# PCB-SSB-2x4b.net
KiCad netlist of a schematic drawn in EAGLE
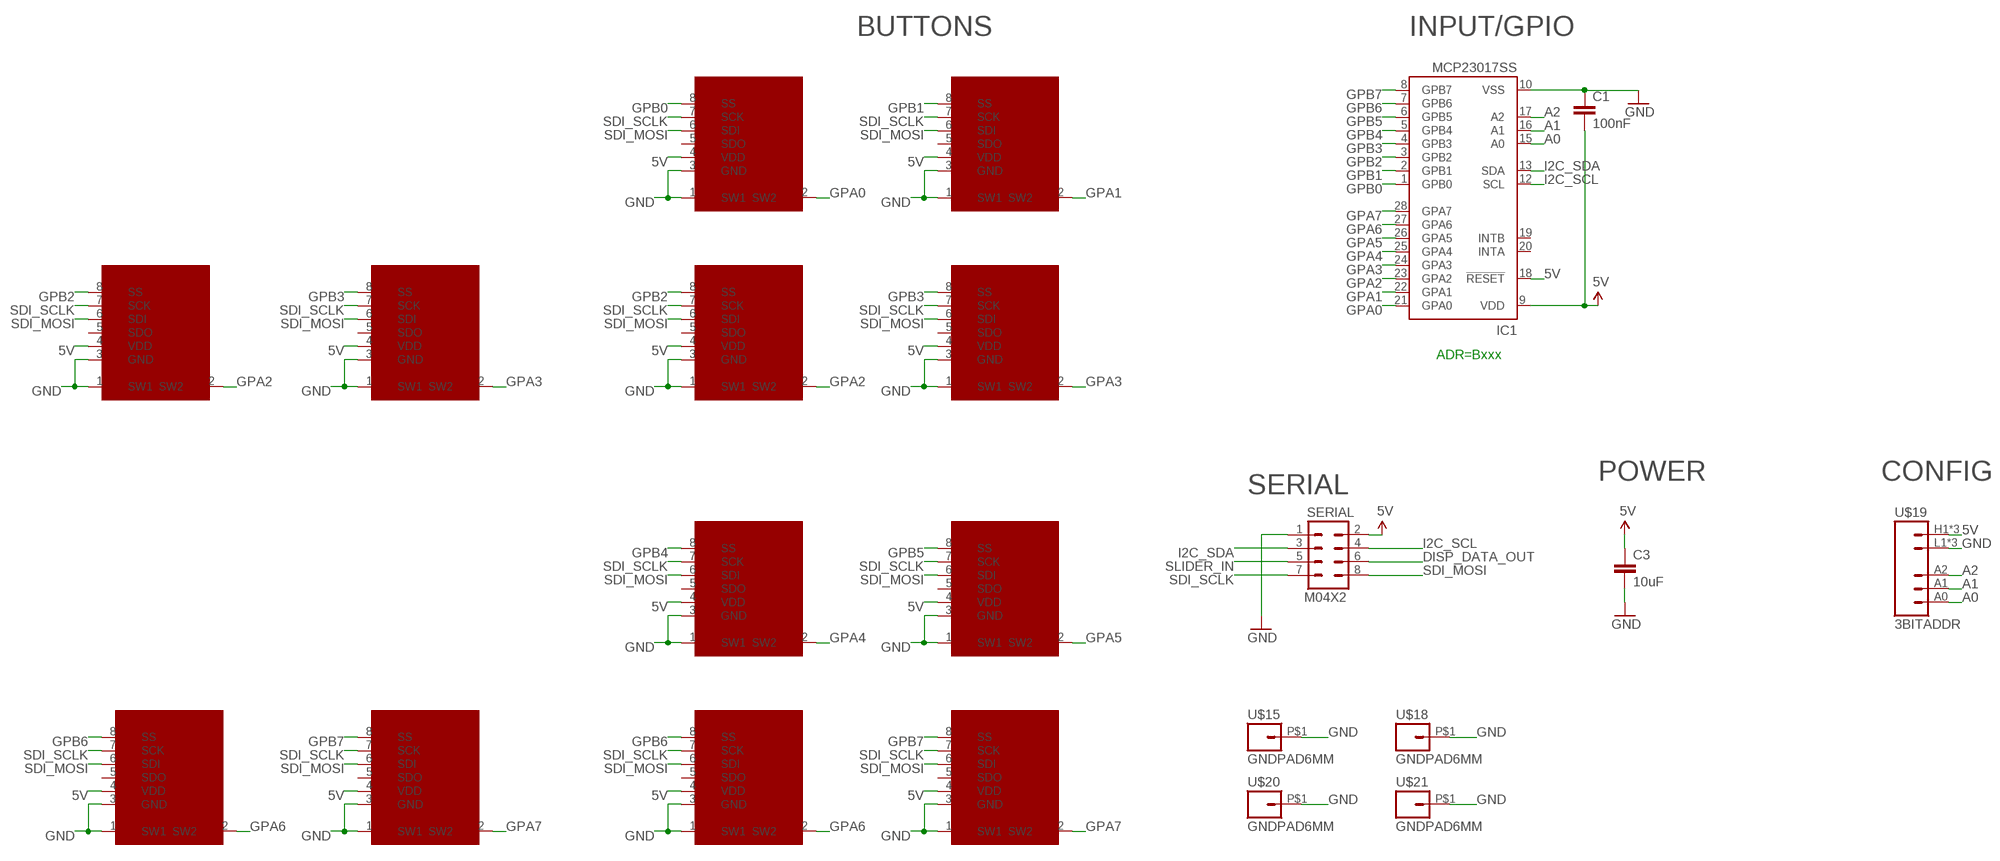
[diagram p0: schematic, sheet 1]

(export (version "E")
  (design (tool "Eeschema 10.0.6"))
  (components
    (comp (ref "C1")
      (value "100nF")
      (footprint "eagle-import:0603-CAP")
      (libsource (lib "eagle-import") (part "CAP0603-CAP"))
    )
    (comp (ref "C3")
      (value "10uF")
      (footprint "eagle-import:0805")
      (libsource (lib "eagle-import") (part "CAP0805"))
    )
    (comp (ref "IC1")
      (value "MCP23017SS")
      (footprint "eagle-import:SSOP28")
      (fields
        (field (name "MF") "MICROCHIP")
        (field (name "MPN") "MCP23017-E/SS")
        (field (name "MPN_1") "MCP23017-E/SS")
        (field (name "OC_FARNELL") "1467674")
        (field (name "OC_NEWARK") "31K2960")
      )
      (libsource (lib "eagle-import") (part "MCP23017SS"))
    )
    (comp (ref "SERIAL")
      (value "M04X2")
      (footprint "eagle-import:2X4")
      (libsource (lib "eagle-import") (part "M04X2"))
    )
    (comp (ref "SSW1")
      (value "SMART_SWITCHSMART_SWITCH_8PIN")
      (footprint "eagle-import:SMART_SWITCH")
      (libsource (lib "eagle-import") (part "SMART_SWITCHSMART_SWITCH_8PIN"))
    )
    (comp (ref "SSW2")
      (value "SMART_SWITCHSMART_SWITCH_8PIN")
      (footprint "eagle-import:SMART_SWITCH")
      (libsource (lib "eagle-import") (part "SMART_SWITCHSMART_SWITCH_8PIN"))
    )
    (comp (ref "SSW3")
      (value "SMART_SWITCHSMART_SWITCH_8PIN")
      (footprint "eagle-import:SMART_SWITCH")
      (libsource (lib "eagle-import") (part "SMART_SWITCHSMART_SWITCH_8PIN"))
    )
    (comp (ref "SSW3ALT")
      (value "SMART_SWITCHSMART_SWITCH_8PIN")
      (footprint "eagle-import:SMART_SWITCH")
      (libsource (lib "eagle-import") (part "SMART_SWITCHSMART_SWITCH_8PIN"))
    )
    (comp (ref "SSW4")
      (value "SMART_SWITCHSMART_SWITCH_8PIN")
      (footprint "eagle-import:SMART_SWITCH")
      (libsource (lib "eagle-import") (part "SMART_SWITCHSMART_SWITCH_8PIN"))
    )
    (comp (ref "SSW4ALT")
      (value "SMART_SWITCHSMART_SWITCH_8PIN")
      (footprint "eagle-import:SMART_SWITCH")
      (libsource (lib "eagle-import") (part "SMART_SWITCHSMART_SWITCH_8PIN"))
    )
    (comp (ref "SSW5")
      (value "SMART_SWITCHSMART_SWITCH_8PIN")
      (footprint "eagle-import:SMART_SWITCH")
      (libsource (lib "eagle-import") (part "SMART_SWITCHSMART_SWITCH_8PIN"))
    )
    (comp (ref "SSW6")
      (value "SMART_SWITCHSMART_SWITCH_8PIN")
      (footprint "eagle-import:SMART_SWITCH")
      (libsource (lib "eagle-import") (part "SMART_SWITCHSMART_SWITCH_8PIN"))
    )
    (comp (ref "SSW7")
      (value "SMART_SWITCHSMART_SWITCH_8PIN")
      (footprint "eagle-import:SMART_SWITCH")
      (libsource (lib "eagle-import") (part "SMART_SWITCHSMART_SWITCH_8PIN"))
    )
    (comp (ref "SSW7ALT")
      (value "SMART_SWITCHSMART_SWITCH_8PIN")
      (footprint "eagle-import:SMART_SWITCH")
      (libsource (lib "eagle-import") (part "SMART_SWITCHSMART_SWITCH_8PIN"))
    )
    (comp (ref "SSW8")
      (value "SMART_SWITCHSMART_SWITCH_8PIN")
      (footprint "eagle-import:SMART_SWITCH")
      (libsource (lib "eagle-import") (part "SMART_SWITCHSMART_SWITCH_8PIN"))
    )
    (comp (ref "SSW8ALT")
      (value "SMART_SWITCHSMART_SWITCH_8PIN")
      (footprint "eagle-import:SMART_SWITCH")
      (libsource (lib "eagle-import") (part "SMART_SWITCHSMART_SWITCH_8PIN"))
    )
    (comp (ref "U$15")
      (value "GNDPAD6MM")
      (footprint "eagle-import:3.2MMPAD6MM")
      (libsource (lib "eagle-import") (part "GNDPAD6MM"))
    )
    (comp (ref "U$18")
      (value "GNDPAD6MM")
      (footprint "eagle-import:3.2MMPAD6MM")
      (libsource (lib "eagle-import") (part "GNDPAD6MM"))
    )
    (comp (ref "U$19")
      (value "3BITADDR")
      (footprint "eagle-import:3BITADDR")
      (libsource (lib "eagle-import") (part "3BITADDR"))
    )
    (comp (ref "U$20")
      (value "GNDPAD6MM")
      (footprint "eagle-import:3.2MMPAD6MM")
      (libsource (lib "eagle-import") (part "GNDPAD6MM"))
    )
    (comp (ref "U$21")
      (value "GNDPAD6MM")
      (footprint "eagle-import:3.2MMPAD6MM")
      (libsource (lib "eagle-import") (part "GNDPAD6MM"))
    )
  )
  (nets
    (net (code "1") (name "/A0") (class "Default")
      (node (ref "IC1") (pin "15") (pinfunction "A0_15") (pintype "input"))
      (node (ref "U$19") (pin "A0") (pinfunction "A0_A0") (pintype "passive"))
    )
    (net (code "2") (name "/A1") (class "Default")
      (node (ref "IC1") (pin "16") (pinfunction "A1_16") (pintype "input"))
      (node (ref "U$19") (pin "A1") (pinfunction "A1_A1") (pintype "passive"))
    )
    (net (code "3") (name "/A2") (class "Default")
      (node (ref "IC1") (pin "17") (pinfunction "A2_17") (pintype "input"))
      (node (ref "U$19") (pin "A2") (pinfunction "A2_A2") (pintype "passive"))
    )
    (net (code "4") (name "/DISP_DATA_OUT") (class "Default")
      (node (ref "SERIAL") (pin "6") (pinfunction "6_6") (pintype "passive"))
    )
    (net (code "5") (name "/GPA0") (class "Default")
      (node (ref "IC1") (pin "21") (pinfunction "GPA0_21") (pintype "bidirectional"))
      (node (ref "SSW1") (pin "2") (pinfunction "SW2_2") (pintype "bidirectional"))
    )
    (net (code "6") (name "/GPA1") (class "Default")
      (node (ref "IC1") (pin "22") (pinfunction "GPA1_22") (pintype "bidirectional"))
      (node (ref "SSW2") (pin "2") (pinfunction "SW2_2") (pintype "bidirectional"))
    )
    (net (code "7") (name "/GPA2") (class "Default")
      (node (ref "IC1") (pin "23") (pinfunction "GPA2_23") (pintype "bidirectional"))
      (node (ref "SSW3") (pin "2") (pinfunction "SW2_2") (pintype "bidirectional"))
      (node (ref "SSW3ALT") (pin "2") (pinfunction "SW2_2") (pintype "bidirectional"))
    )
    (net (code "8") (name "/GPA3") (class "Default")
      (node (ref "IC1") (pin "24") (pinfunction "GPA3_24") (pintype "bidirectional"))
      (node (ref "SSW4") (pin "2") (pinfunction "SW2_2") (pintype "bidirectional"))
      (node (ref "SSW4ALT") (pin "2") (pinfunction "SW2_2") (pintype "bidirectional"))
    )
    (net (code "9") (name "/GPA4") (class "Default")
      (node (ref "IC1") (pin "25") (pinfunction "GPA4_25") (pintype "bidirectional"))
      (node (ref "SSW5") (pin "2") (pinfunction "SW2_2") (pintype "bidirectional"))
    )
    (net (code "10") (name "/GPA5") (class "Default")
      (node (ref "IC1") (pin "26") (pinfunction "GPA5_26") (pintype "bidirectional"))
      (node (ref "SSW6") (pin "2") (pinfunction "SW2_2") (pintype "bidirectional"))
    )
    (net (code "11") (name "/GPA6") (class "Default")
      (node (ref "IC1") (pin "27") (pinfunction "GPA6_27") (pintype "bidirectional"))
      (node (ref "SSW7") (pin "2") (pinfunction "SW2_2") (pintype "bidirectional"))
      (node (ref "SSW7ALT") (pin "2") (pinfunction "SW2_2") (pintype "bidirectional"))
    )
    (net (code "12") (name "/GPA7") (class "Default")
      (node (ref "IC1") (pin "28") (pinfunction "GPA7_28") (pintype "bidirectional"))
      (node (ref "SSW8") (pin "2") (pinfunction "SW2_2") (pintype "bidirectional"))
      (node (ref "SSW8ALT") (pin "2") (pinfunction "SW2_2") (pintype "bidirectional"))
    )
    (net (code "13") (name "/GPB0") (class "Default")
      (node (ref "IC1") (pin "1") (pinfunction "GPB0_1") (pintype "bidirectional"))
      (node (ref "SSW1") (pin "8") (pinfunction "SS_8") (pintype "bidirectional"))
    )
    (net (code "14") (name "/GPB1") (class "Default")
      (node (ref "IC1") (pin "2") (pinfunction "GPB1_2") (pintype "bidirectional"))
      (node (ref "SSW2") (pin "8") (pinfunction "SS_8") (pintype "bidirectional"))
    )
    (net (code "15") (name "/GPB2") (class "Default")
      (node (ref "IC1") (pin "3") (pinfunction "GPB2_3") (pintype "bidirectional"))
      (node (ref "SSW3") (pin "8") (pinfunction "SS_8") (pintype "bidirectional"))
      (node (ref "SSW3ALT") (pin "8") (pinfunction "SS_8") (pintype "bidirectional"))
    )
    (net (code "16") (name "/GPB3") (class "Default")
      (node (ref "IC1") (pin "4") (pinfunction "GPB3_4") (pintype "bidirectional"))
      (node (ref "SSW4") (pin "8") (pinfunction "SS_8") (pintype "bidirectional"))
      (node (ref "SSW4ALT") (pin "8") (pinfunction "SS_8") (pintype "bidirectional"))
    )
    (net (code "17") (name "/GPB4") (class "Default")
      (node (ref "IC1") (pin "5") (pinfunction "GPB4_5") (pintype "bidirectional"))
      (node (ref "SSW5") (pin "8") (pinfunction "SS_8") (pintype "bidirectional"))
    )
    (net (code "18") (name "/GPB5") (class "Default")
      (node (ref "IC1") (pin "6") (pinfunction "GPB5_6") (pintype "bidirectional"))
      (node (ref "SSW6") (pin "8") (pinfunction "SS_8") (pintype "bidirectional"))
    )
    (net (code "19") (name "/GPB6") (class "Default")
      (node (ref "IC1") (pin "7") (pinfunction "GPB6_7") (pintype "bidirectional"))
      (node (ref "SSW7") (pin "8") (pinfunction "SS_8") (pintype "bidirectional"))
      (node (ref "SSW7ALT") (pin "8") (pinfunction "SS_8") (pintype "bidirectional"))
    )
    (net (code "20") (name "/GPB7") (class "Default")
      (node (ref "IC1") (pin "8") (pinfunction "GPB7_8") (pintype "bidirectional"))
      (node (ref "SSW8") (pin "8") (pinfunction "SS_8") (pintype "bidirectional"))
      (node (ref "SSW8ALT") (pin "8") (pinfunction "SS_8") (pintype "bidirectional"))
    )
    (net (code "21") (name "/I2C_SCL") (class "Default")
      (node (ref "IC1") (pin "12") (pinfunction "SCL_12") (pintype "input"))
      (node (ref "SERIAL") (pin "4") (pinfunction "4_4") (pintype "passive"))
    )
    (net (code "22") (name "/I2C_SDA") (class "Default")
      (node (ref "IC1") (pin "13") (pinfunction "SDA_13") (pintype "bidirectional"))
      (node (ref "SERIAL") (pin "3") (pinfunction "3_3") (pintype "passive"))
    )
    (net (code "23") (name "/SDI_MOSI") (class "Default")
      (node (ref "SERIAL") (pin "8") (pinfunction "8_8") (pintype "passive"))
      (node (ref "SSW1") (pin "6") (pinfunction "SDI_6") (pintype "bidirectional"))
      (node (ref "SSW2") (pin "6") (pinfunction "SDI_6") (pintype "bidirectional"))
      (node (ref "SSW3") (pin "6") (pinfunction "SDI_6") (pintype "bidirectional"))
      (node (ref "SSW3ALT") (pin "6") (pinfunction "SDI_6") (pintype "bidirectional"))
      (node (ref "SSW4") (pin "6") (pinfunction "SDI_6") (pintype "bidirectional"))
      (node (ref "SSW4ALT") (pin "6") (pinfunction "SDI_6") (pintype "bidirectional"))
      (node (ref "SSW5") (pin "6") (pinfunction "SDI_6") (pintype "bidirectional"))
      (node (ref "SSW6") (pin "6") (pinfunction "SDI_6") (pintype "bidirectional"))
      (node (ref "SSW7") (pin "6") (pinfunction "SDI_6") (pintype "bidirectional"))
      (node (ref "SSW7ALT") (pin "6") (pinfunction "SDI_6") (pintype "bidirectional"))
      (node (ref "SSW8") (pin "6") (pinfunction "SDI_6") (pintype "bidirectional"))
      (node (ref "SSW8ALT") (pin "6") (pinfunction "SDI_6") (pintype "bidirectional"))
    )
    (net (code "24") (name "/SDI_SCLK") (class "Default")
      (node (ref "SERIAL") (pin "7") (pinfunction "7_7") (pintype "passive"))
      (node (ref "SSW1") (pin "7") (pinfunction "SCK_7") (pintype "bidirectional"))
      (node (ref "SSW2") (pin "7") (pinfunction "SCK_7") (pintype "bidirectional"))
      (node (ref "SSW3") (pin "7") (pinfunction "SCK_7") (pintype "bidirectional"))
      (node (ref "SSW3ALT") (pin "7") (pinfunction "SCK_7") (pintype "bidirectional"))
      (node (ref "SSW4") (pin "7") (pinfunction "SCK_7") (pintype "bidirectional"))
      (node (ref "SSW4ALT") (pin "7") (pinfunction "SCK_7") (pintype "bidirectional"))
      (node (ref "SSW5") (pin "7") (pinfunction "SCK_7") (pintype "bidirectional"))
      (node (ref "SSW6") (pin "7") (pinfunction "SCK_7") (pintype "bidirectional"))
      (node (ref "SSW7") (pin "7") (pinfunction "SCK_7") (pintype "bidirectional"))
      (node (ref "SSW7ALT") (pin "7") (pinfunction "SCK_7") (pintype "bidirectional"))
      (node (ref "SSW8") (pin "7") (pinfunction "SCK_7") (pintype "bidirectional"))
      (node (ref "SSW8ALT") (pin "7") (pinfunction "SCK_7") (pintype "bidirectional"))
    )
    (net (code "25") (name "/SLIDER_IN") (class "Default")
      (node (ref "SERIAL") (pin "5") (pinfunction "5_5") (pintype "passive"))
    )
    (net (code "26") (name "5V") (class "Default")
      (node (ref "C1") (pin "2") (pinfunction "2_2") (pintype "passive"))
      (node (ref "C3") (pin "1") (pinfunction "1_1") (pintype "passive"))
      (node (ref "IC1") (pin "18") (pinfunction "~{RESET}_18") (pintype "input"))
      (node (ref "IC1") (pin "9") (pinfunction "VDD_9") (pintype "power_in"))
      (node (ref "SERIAL") (pin "2") (pinfunction "2_2") (pintype "passive"))
      (node (ref "SSW1") (pin "4") (pinfunction "VDD_4") (pintype "bidirectional"))
      (node (ref "SSW2") (pin "4") (pinfunction "VDD_4") (pintype "bidirectional"))
      (node (ref "SSW3") (pin "4") (pinfunction "VDD_4") (pintype "bidirectional"))
      (node (ref "SSW3ALT") (pin "4") (pinfunction "VDD_4") (pintype "bidirectional"))
      (node (ref "SSW4") (pin "4") (pinfunction "VDD_4") (pintype "bidirectional"))
      (node (ref "SSW4ALT") (pin "4") (pinfunction "VDD_4") (pintype "bidirectional"))
      (node (ref "SSW5") (pin "4") (pinfunction "VDD_4") (pintype "bidirectional"))
      (node (ref "SSW6") (pin "4") (pinfunction "VDD_4") (pintype "bidirectional"))
      (node (ref "SSW7") (pin "4") (pinfunction "VDD_4") (pintype "bidirectional"))
      (node (ref "SSW7ALT") (pin "4") (pinfunction "VDD_4") (pintype "bidirectional"))
      (node (ref "SSW8") (pin "4") (pinfunction "VDD_4") (pintype "bidirectional"))
      (node (ref "SSW8ALT") (pin "4") (pinfunction "VDD_4") (pintype "bidirectional"))
      (node (ref "U$19") (pin "H1") (pinfunction "VCC_H1") (pintype "passive"))
      (node (ref "U$19") (pin "H2") (pinfunction "VCC_H2") (pintype "passive"))
      (node (ref "U$19") (pin "H3") (pinfunction "VCC_H3") (pintype "passive"))
    )
    (net (code "27") (name "GND") (class "Default")
      (node (ref "C1") (pin "1") (pinfunction "1_1") (pintype "passive"))
      (node (ref "C3") (pin "2") (pinfunction "2_2") (pintype "passive"))
      (node (ref "IC1") (pin "10") (pinfunction "VSS_10") (pintype "power_in"))
      (node (ref "SERIAL") (pin "1") (pinfunction "1_1") (pintype "passive"))
      (node (ref "SSW1") (pin "1") (pinfunction "SW1_1") (pintype "bidirectional"))
      (node (ref "SSW1") (pin "3") (pinfunction "GND_3") (pintype "bidirectional"))
      (node (ref "SSW2") (pin "1") (pinfunction "SW1_1") (pintype "bidirectional"))
      (node (ref "SSW2") (pin "3") (pinfunction "GND_3") (pintype "bidirectional"))
      (node (ref "SSW3") (pin "1") (pinfunction "SW1_1") (pintype "bidirectional"))
      (node (ref "SSW3") (pin "3") (pinfunction "GND_3") (pintype "bidirectional"))
      (node (ref "SSW3ALT") (pin "1") (pinfunction "SW1_1") (pintype "bidirectional"))
      (node (ref "SSW3ALT") (pin "3") (pinfunction "GND_3") (pintype "bidirectional"))
      (node (ref "SSW4") (pin "1") (pinfunction "SW1_1") (pintype "bidirectional"))
      (node (ref "SSW4") (pin "3") (pinfunction "GND_3") (pintype "bidirectional"))
      (node (ref "SSW4ALT") (pin "1") (pinfunction "SW1_1") (pintype "bidirectional"))
      (node (ref "SSW4ALT") (pin "3") (pinfunction "GND_3") (pintype "bidirectional"))
      (node (ref "SSW5") (pin "1") (pinfunction "SW1_1") (pintype "bidirectional"))
      (node (ref "SSW5") (pin "3") (pinfunction "GND_3") (pintype "bidirectional"))
      (node (ref "SSW6") (pin "1") (pinfunction "SW1_1") (pintype "bidirectional"))
      (node (ref "SSW6") (pin "3") (pinfunction "GND_3") (pintype "bidirectional"))
      (node (ref "SSW7") (pin "1") (pinfunction "SW1_1") (pintype "bidirectional"))
      (node (ref "SSW7") (pin "3") (pinfunction "GND_3") (pintype "bidirectional"))
      (node (ref "SSW7ALT") (pin "1") (pinfunction "SW1_1") (pintype "bidirectional"))
      (node (ref "SSW7ALT") (pin "3") (pinfunction "GND_3") (pintype "bidirectional"))
      (node (ref "SSW8") (pin "1") (pinfunction "SW1_1") (pintype "bidirectional"))
      (node (ref "SSW8") (pin "3") (pinfunction "GND_3") (pintype "bidirectional"))
      (node (ref "SSW8ALT") (pin "1") (pinfunction "SW1_1") (pintype "bidirectional"))
      (node (ref "SSW8ALT") (pin "3") (pinfunction "GND_3") (pintype "bidirectional"))
      (node (ref "U$15") (pin "P$1") (pinfunction "1_P$1") (pintype "passive"))
      (node (ref "U$18") (pin "P$1") (pinfunction "1_P$1") (pintype "passive"))
      (node (ref "U$19") (pin "L1") (pinfunction "GND_L1") (pintype "passive"))
      (node (ref "U$19") (pin "L2") (pinfunction "GND_L2") (pintype "passive"))
      (node (ref "U$19") (pin "L3") (pinfunction "GND_L3") (pintype "passive"))
      (node (ref "U$20") (pin "P$1") (pinfunction "1_P$1") (pintype "passive"))
      (node (ref "U$21") (pin "P$1") (pinfunction "1_P$1") (pintype "passive"))
    )
    (net (code "28") (name "unconnected-(IC1-INTA-Pad20)") (class "Default")
      (node (ref "IC1") (pin "20") (pinfunction "INTA_20") (pintype "output"))
    )
    (net (code "29") (name "unconnected-(IC1-INTB-Pad19)") (class "Default")
      (node (ref "IC1") (pin "19") (pinfunction "INTB_19") (pintype "output"))
    )
    (net (code "30") (name "unconnected-(SSW1-SDO-Pad5)") (class "Default")
      (node (ref "SSW1") (pin "5") (pinfunction "SDO_5") (pintype "bidirectional"))
    )
    (net (code "31") (name "unconnected-(SSW2-SDO-Pad5)") (class "Default")
      (node (ref "SSW2") (pin "5") (pinfunction "SDO_5") (pintype "bidirectional"))
    )
    (net (code "32") (name "unconnected-(SSW3-SDO-Pad5)") (class "Default")
      (node (ref "SSW3") (pin "5") (pinfunction "SDO_5") (pintype "bidirectional"))
    )
    (net (code "33") (name "unconnected-(SSW3ALT-SDO-Pad5)") (class "Default")
      (node (ref "SSW3ALT") (pin "5") (pinfunction "SDO_5") (pintype "bidirectional"))
    )
    (net (code "34") (name "unconnected-(SSW4-SDO-Pad5)") (class "Default")
      (node (ref "SSW4") (pin "5") (pinfunction "SDO_5") (pintype "bidirectional"))
    )
    (net (code "35") (name "unconnected-(SSW4ALT-SDO-Pad5)") (class "Default")
      (node (ref "SSW4ALT") (pin "5") (pinfunction "SDO_5") (pintype "bidirectional"))
    )
    (net (code "36") (name "unconnected-(SSW5-SDO-Pad5)") (class "Default")
      (node (ref "SSW5") (pin "5") (pinfunction "SDO_5") (pintype "bidirectional"))
    )
    (net (code "37") (name "unconnected-(SSW6-SDO-Pad5)") (class "Default")
      (node (ref "SSW6") (pin "5") (pinfunction "SDO_5") (pintype "bidirectional"))
    )
    (net (code "38") (name "unconnected-(SSW7-SDO-Pad5)") (class "Default")
      (node (ref "SSW7") (pin "5") (pinfunction "SDO_5") (pintype "bidirectional"))
    )
    (net (code "39") (name "unconnected-(SSW7ALT-SDO-Pad5)") (class "Default")
      (node (ref "SSW7ALT") (pin "5") (pinfunction "SDO_5") (pintype "bidirectional"))
    )
    (net (code "40") (name "unconnected-(SSW8-SDO-Pad5)") (class "Default")
      (node (ref "SSW8") (pin "5") (pinfunction "SDO_5") (pintype "bidirectional"))
    )
    (net (code "41") (name "unconnected-(SSW8ALT-SDO-Pad5)") (class "Default")
      (node (ref "SSW8ALT") (pin "5") (pinfunction "SDO_5") (pintype "bidirectional"))
    )
  )
)
